# Schematic.net
KiCad netlist of a schematic drawn in EAGLE
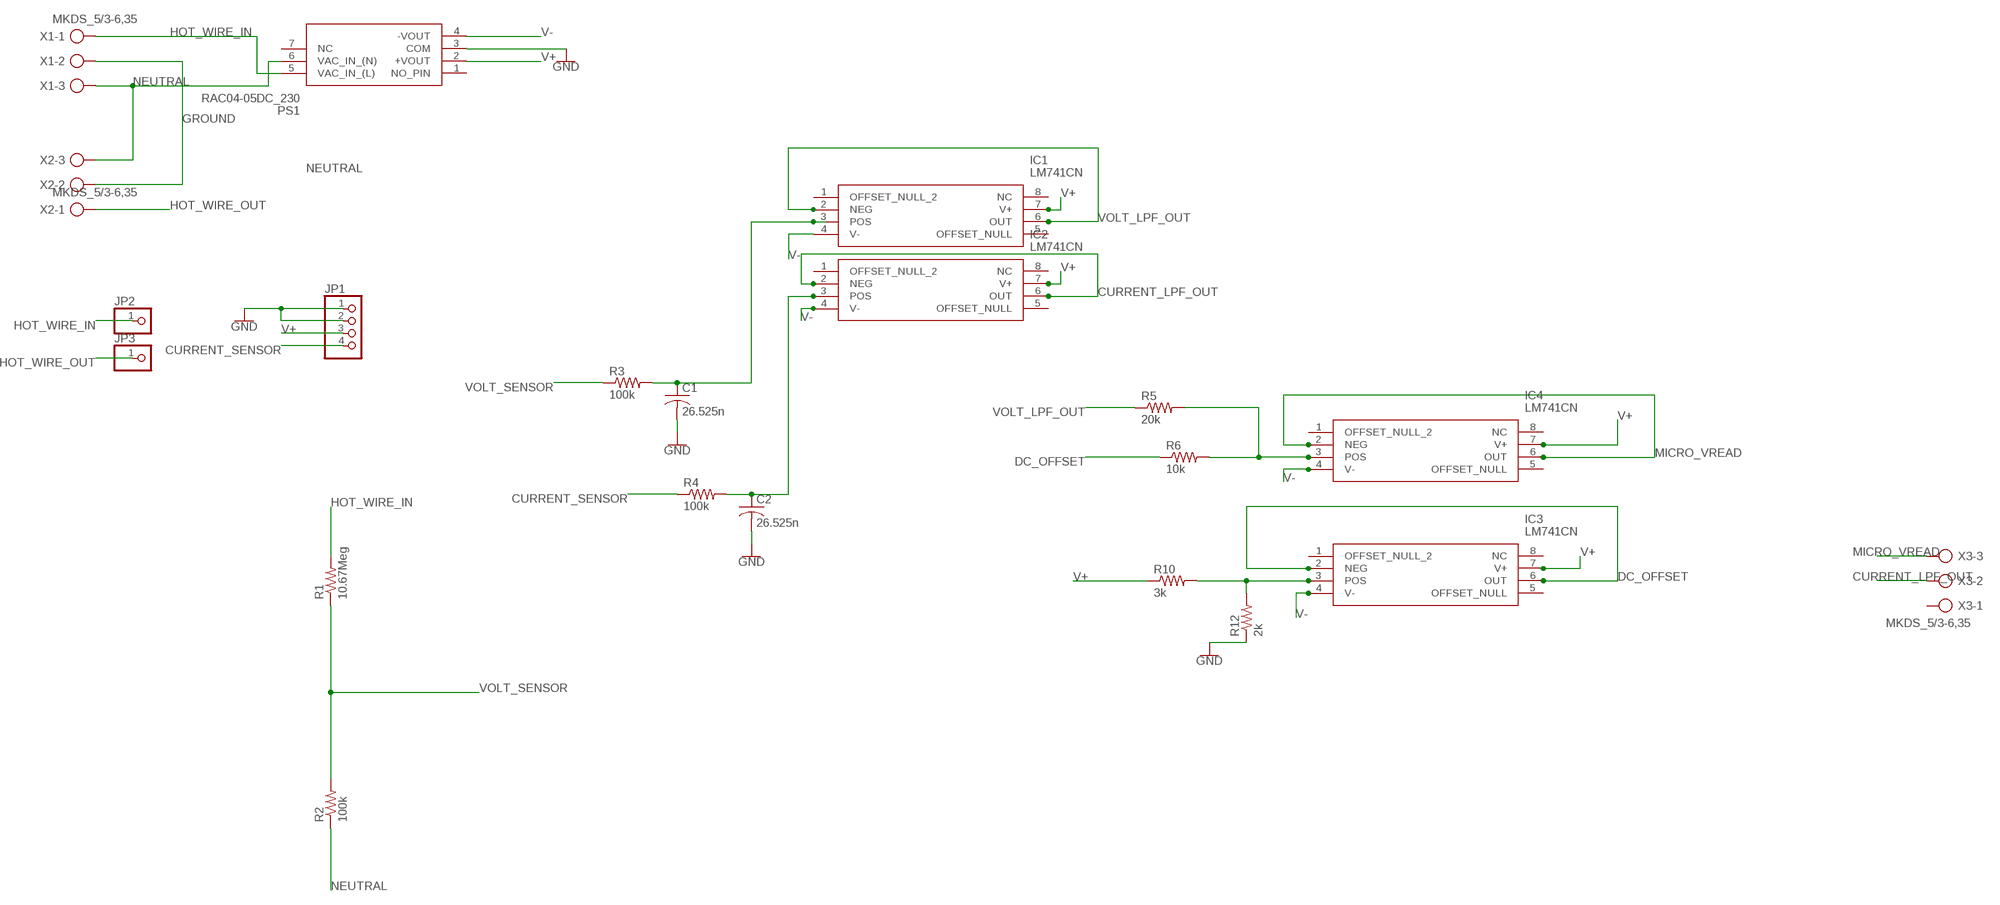
[diagram p0: schematic, sheet 1]

(export (version "E")
  (design (tool "Eeschema 10.0.6"))
  (components
    (comp (ref "C1")
      (value "26.525n")
      (footprint "eagle-import:C025-040X050")
      (fields (field (name "MPN") "MC0805B224K500A5.08MM"))
      (libsource (lib "eagle-import") (part "C-US025-040X050"))
    )
    (comp (ref "C2")
      (value "26.525n")
      (footprint "eagle-import:C025-040X050")
      (fields (field (name "MPN") "MC0805B224K500A5.08MM"))
      (libsource (lib "eagle-import") (part "C-US025-040X050"))
    )
    (comp (ref "IC1")
      (value "LM741CN")
      (footprint "eagle-import:DIP254P762X508-8")
      (fields (field (name "RS_PART_NUMBER") "4718749"))
      (libsource (lib "eagle-import") (part "LM741CN"))
    )
    (comp (ref "IC2")
      (value "LM741CN")
      (footprint "eagle-import:DIP254P762X508-8")
      (fields (field (name "RS_PART_NUMBER") "4718749"))
      (libsource (lib "eagle-import") (part "LM741CN"))
    )
    (comp (ref "IC3")
      (value "LM741CN")
      (footprint "eagle-import:DIP254P762X508-8")
      (fields (field (name "RS_PART_NUMBER") "4718749"))
      (libsource (lib "eagle-import") (part "LM741CN"))
    )
    (comp (ref "IC4")
      (value "LM741CN")
      (footprint "eagle-import:DIP254P762X508-8")
      (fields (field (name "RS_PART_NUMBER") "4718749"))
      (libsource (lib "eagle-import") (part "LM741CN"))
    )
    (comp (ref "JP1")
      (value "PINHD-1X4")
      (footprint "eagle-import:1X04")
      (libsource (lib "eagle-import") (part "PINHD-1X4"))
    )
    (comp (ref "JP2")
      (value "PINHD-1X1")
      (footprint "eagle-import:1X01")
      (libsource (lib "eagle-import") (part "PINHD-1X1"))
    )
    (comp (ref "JP3")
      (value "PINHD-1X1")
      (footprint "eagle-import:1X01")
      (libsource (lib "eagle-import") (part "PINHD-1X1"))
    )
    (comp (ref "PS1")
      (value "RAC04-05DC_230")
      (footprint "eagle-import:RAC04-0512DC230")
      (fields
        (field (name "MANUFACTURER_PART_NUMBER") "RAC04-05DC/230")
        (field (name "RS_PART_NUMBER") "1666726")
      )
      (libsource (lib "eagle-import") (part "RAC04-05DC_230"))
    )
    (comp (ref "R1")
      (value "10.67Meg")
      (footprint "eagle-import:0617_22")
      (libsource (lib "eagle-import") (part "R-US_0617/22"))
    )
    (comp (ref "R2")
      (value "100k")
      (footprint "eagle-import:0617_22")
      (fields (field (name "MPN") "MFR3-100KFC"))
      (libsource (lib "eagle-import") (part "R-US_0617/22"))
    )
    (comp (ref "R3")
      (value "100k")
      (footprint "eagle-import:0617_22")
      (fields (field (name "MPN") "MFR3-1K0FC"))
      (libsource (lib "eagle-import") (part "R-US_0617/22"))
    )
    (comp (ref "R4")
      (value "100k")
      (footprint "eagle-import:0617_22")
      (fields (field (name "MPN") "MFR3-1K0FC"))
      (libsource (lib "eagle-import") (part "R-US_0617/22"))
    )
    (comp (ref "R5")
      (value "20k")
      (footprint "eagle-import:0617_22")
      (fields (field (name "MPN") "MFR4-20KFI"))
      (libsource (lib "eagle-import") (part "R-US_0617/22"))
    )
    (comp (ref "R6")
      (value "10k")
      (footprint "eagle-import:0617_22")
      (fields (field (name "MPN") "CCF5510K0FKE36"))
      (libsource (lib "eagle-import") (part "R-US_0617/22"))
    )
    (comp (ref "R10")
      (value "3k")
      (footprint "eagle-import:0617_22")
      (fields (field (name "MPN") "MFR4 3K3 1%"))
      (libsource (lib "eagle-import") (part "R-US_0617/22"))
    )
    (comp (ref "R12")
      (value "2k")
      (footprint "eagle-import:0617_22")
      (fields (field (name "MPN") "MFR4-2K0FI"))
      (libsource (lib "eagle-import") (part "R-US_0617/22"))
    )
    (comp (ref "X1")
      (value "MKDS_5/3-6,35")
      (footprint "eagle-import:MKDS_5_3-635")
      (fields (field (name "MF") "FARNELL") (field (name "MPN") "1714968"))
      (libsource (lib "eagle-import") (part "MKDS_5/3-6,35"))
    )
    (comp (ref "X2")
      (value "MKDS_5/3-6,35")
      (footprint "eagle-import:MKDS_5_3-635")
      (fields (field (name "MF") "FARNELL") (field (name "MPN") "1714968"))
      (libsource (lib "eagle-import") (part "MKDS_5/3-6,35"))
    )
    (comp (ref "X3")
      (value "MKDS_5/3-6,35")
      (footprint "eagle-import:MKDS_5_3-635")
      (fields (field (name "MF") "FARNELL") (field (name "MPN") "1714968") (field (name "SPICEPREFIX") "X"))
      (libsource (lib "eagle-import") (part "MKDS_5/3-6,35"))
    )
  )
  (nets
    (net (code "1") (name "/CURRENT_LPF_OUT") (class "Default")
      (node (ref "IC2") (pin "2") (pinfunction "NEG_2") (pintype "bidirectional"))
      (node (ref "IC2") (pin "6") (pinfunction "OUT_6") (pintype "bidirectional"))
      (node (ref "X3") (pin "2") (pinfunction "KL_2") (pintype "passive"))
    )
    (net (code "2") (name "/CURRENT_SENSOR") (class "Default")
      (node (ref "JP1") (pin "4") (pinfunction "4_4") (pintype "passive"))
      (node (ref "R4") (pin "1") (pinfunction "1_1") (pintype "passive"))
    )
    (net (code "3") (name "/DC_OFFSET") (class "Default")
      (node (ref "IC3") (pin "2") (pinfunction "NEG_2") (pintype "bidirectional"))
      (node (ref "IC3") (pin "6") (pinfunction "OUT_6") (pintype "bidirectional"))
      (node (ref "R6") (pin "1") (pinfunction "1_1") (pintype "passive"))
    )
    (net (code "4") (name "/GROUND") (class "Default")
      (node (ref "X1") (pin "2") (pinfunction "KL_2") (pintype "passive"))
      (node (ref "X2") (pin "2") (pinfunction "KL_2") (pintype "passive"))
    )
    (net (code "5") (name "/HOT_WIRE_IN") (class "Default")
      (node (ref "JP2") (pin "1") (pinfunction "1_1") (pintype "passive"))
      (node (ref "PS1") (pin "5") (pinfunction "VAC_IN_(L)_5") (pintype "bidirectional"))
      (node (ref "R1") (pin "2") (pinfunction "2_2") (pintype "passive"))
      (node (ref "X1") (pin "1") (pinfunction "KL_1") (pintype "passive"))
    )
    (net (code "6") (name "/HOT_WIRE_OUT") (class "Default")
      (node (ref "JP3") (pin "1") (pinfunction "1_1") (pintype "passive"))
      (node (ref "X2") (pin "1") (pinfunction "KL_1") (pintype "passive"))
    )
    (net (code "7") (name "/MICRO_VREAD") (class "Default")
      (node (ref "IC4") (pin "2") (pinfunction "NEG_2") (pintype "bidirectional"))
      (node (ref "IC4") (pin "6") (pinfunction "OUT_6") (pintype "bidirectional"))
      (node (ref "X3") (pin "3") (pinfunction "KL_3") (pintype "passive"))
    )
    (net (code "8") (name "/NEUTRAL") (class "Default")
      (node (ref "PS1") (pin "6") (pinfunction "VAC_IN_(N)_6") (pintype "bidirectional"))
      (node (ref "R2") (pin "1") (pinfunction "1_1") (pintype "passive"))
      (node (ref "X1") (pin "3") (pinfunction "KL_3") (pintype "passive"))
      (node (ref "X2") (pin "3") (pinfunction "KL_3") (pintype "passive"))
    )
    (net (code "9") (name "/V+") (class "Default")
      (node (ref "IC1") (pin "7") (pinfunction "V+_7") (pintype "bidirectional"))
      (node (ref "IC2") (pin "7") (pinfunction "V+_7") (pintype "bidirectional"))
      (node (ref "IC3") (pin "7") (pinfunction "V+_7") (pintype "bidirectional"))
      (node (ref "IC4") (pin "7") (pinfunction "V+_7") (pintype "bidirectional"))
      (node (ref "JP1") (pin "3") (pinfunction "3_3") (pintype "passive"))
      (node (ref "PS1") (pin "2") (pinfunction "+VOUT_2") (pintype "bidirectional"))
      (node (ref "R10") (pin "1") (pinfunction "1_1") (pintype "passive"))
    )
    (net (code "10") (name "/V-") (class "Default")
      (node (ref "IC1") (pin "4") (pinfunction "V-_4") (pintype "bidirectional"))
      (node (ref "IC2") (pin "4") (pinfunction "V-_4") (pintype "bidirectional"))
      (node (ref "IC3") (pin "4") (pinfunction "V-_4") (pintype "bidirectional"))
      (node (ref "IC4") (pin "4") (pinfunction "V-_4") (pintype "bidirectional"))
      (node (ref "PS1") (pin "4") (pinfunction "-VOUT_4") (pintype "bidirectional"))
    )
    (net (code "11") (name "/VOLT_LPF_OUT") (class "Default")
      (node (ref "IC1") (pin "2") (pinfunction "NEG_2") (pintype "bidirectional"))
      (node (ref "IC1") (pin "6") (pinfunction "OUT_6") (pintype "bidirectional"))
      (node (ref "R5") (pin "1") (pinfunction "1_1") (pintype "passive"))
    )
    (net (code "12") (name "/VOLT_SENSOR") (class "Default")
      (node (ref "R1") (pin "1") (pinfunction "1_1") (pintype "passive"))
      (node (ref "R2") (pin "2") (pinfunction "2_2") (pintype "passive"))
      (node (ref "R3") (pin "1") (pinfunction "1_1") (pintype "passive"))
    )
    (net (code "13") (name "GND") (class "Default")
      (node (ref "C1") (pin "2") (pinfunction "2_2") (pintype "passive"))
      (node (ref "C2") (pin "2") (pinfunction "2_2") (pintype "passive"))
      (node (ref "JP1") (pin "1") (pinfunction "1_1") (pintype "passive"))
      (node (ref "JP1") (pin "2") (pinfunction "2_2") (pintype "passive"))
      (node (ref "PS1") (pin "3") (pinfunction "COM_3") (pintype "bidirectional"))
      (node (ref "R12") (pin "1") (pinfunction "1_1") (pintype "passive"))
    )
    (net (code "14") (name "Net-(IC1-POS)") (class "Default")
      (node (ref "C1") (pin "1") (pinfunction "1_1") (pintype "passive"))
      (node (ref "IC1") (pin "3") (pinfunction "POS_3") (pintype "bidirectional"))
      (node (ref "R3") (pin "2") (pinfunction "2_2") (pintype "passive"))
    )
    (net (code "15") (name "Net-(IC2-POS)") (class "Default")
      (node (ref "C2") (pin "1") (pinfunction "1_1") (pintype "passive"))
      (node (ref "IC2") (pin "3") (pinfunction "POS_3") (pintype "bidirectional"))
      (node (ref "R4") (pin "2") (pinfunction "2_2") (pintype "passive"))
    )
    (net (code "16") (name "Net-(IC3-POS)") (class "Default")
      (node (ref "IC3") (pin "3") (pinfunction "POS_3") (pintype "bidirectional"))
      (node (ref "R10") (pin "2") (pinfunction "2_2") (pintype "passive"))
      (node (ref "R12") (pin "2") (pinfunction "2_2") (pintype "passive"))
    )
    (net (code "17") (name "Net-(IC4-POS)") (class "Default")
      (node (ref "IC4") (pin "3") (pinfunction "POS_3") (pintype "bidirectional"))
      (node (ref "R5") (pin "2") (pinfunction "2_2") (pintype "passive"))
      (node (ref "R6") (pin "2") (pinfunction "2_2") (pintype "passive"))
    )
    (net (code "18") (name "unconnected-(IC1-NC-Pad8)") (class "Default")
      (node (ref "IC1") (pin "8") (pinfunction "NC_8") (pintype "no_connect"))
    )
    (net (code "19") (name "unconnected-(IC1-OFFSET_NULL-Pad5)") (class "Default")
      (node (ref "IC1") (pin "5") (pinfunction "OFFSET_NULL_5") (pintype "bidirectional"))
    )
    (net (code "20") (name "unconnected-(IC1-OFFSET_NULL_2-Pad1)") (class "Default")
      (node (ref "IC1") (pin "1") (pinfunction "OFFSET_NULL_2_1") (pintype "bidirectional"))
    )
    (net (code "21") (name "unconnected-(IC2-NC-Pad8)") (class "Default")
      (node (ref "IC2") (pin "8") (pinfunction "NC_8") (pintype "no_connect"))
    )
    (net (code "22") (name "unconnected-(IC2-OFFSET_NULL-Pad5)") (class "Default")
      (node (ref "IC2") (pin "5") (pinfunction "OFFSET_NULL_5") (pintype "bidirectional"))
    )
    (net (code "23") (name "unconnected-(IC2-OFFSET_NULL_2-Pad1)") (class "Default")
      (node (ref "IC2") (pin "1") (pinfunction "OFFSET_NULL_2_1") (pintype "bidirectional"))
    )
    (net (code "24") (name "unconnected-(IC3-NC-Pad8)") (class "Default")
      (node (ref "IC3") (pin "8") (pinfunction "NC_8") (pintype "no_connect"))
    )
    (net (code "25") (name "unconnected-(IC3-OFFSET_NULL-Pad5)") (class "Default")
      (node (ref "IC3") (pin "5") (pinfunction "OFFSET_NULL_5") (pintype "bidirectional"))
    )
    (net (code "26") (name "unconnected-(IC3-OFFSET_NULL_2-Pad1)") (class "Default")
      (node (ref "IC3") (pin "1") (pinfunction "OFFSET_NULL_2_1") (pintype "bidirectional"))
    )
    (net (code "27") (name "unconnected-(IC4-NC-Pad8)") (class "Default")
      (node (ref "IC4") (pin "8") (pinfunction "NC_8") (pintype "no_connect"))
    )
    (net (code "28") (name "unconnected-(IC4-OFFSET_NULL-Pad5)") (class "Default")
      (node (ref "IC4") (pin "5") (pinfunction "OFFSET_NULL_5") (pintype "bidirectional"))
    )
    (net (code "29") (name "unconnected-(IC4-OFFSET_NULL_2-Pad1)") (class "Default")
      (node (ref "IC4") (pin "1") (pinfunction "OFFSET_NULL_2_1") (pintype "bidirectional"))
    )
    (net (code "30") (name "unconnected-(PS1-NC-Pad7)") (class "Default")
      (node (ref "PS1") (pin "7") (pinfunction "NC_7") (pintype "no_connect"))
    )
    (net (code "31") (name "unconnected-(PS1-NO_PIN-Pad1)") (class "Default")
      (node (ref "PS1") (pin "1") (pinfunction "NO_PIN_1") (pintype "bidirectional"))
    )
    (net (code "32") (name "unconnected-(X3A-KL-Pad1)") (class "Default")
      (node (ref "X3") (pin "1") (pinfunction "KL_1") (pintype "passive"))
    )
  )
)
